# design.net
KiCad netlist of a schematic drawn in Altium Designer
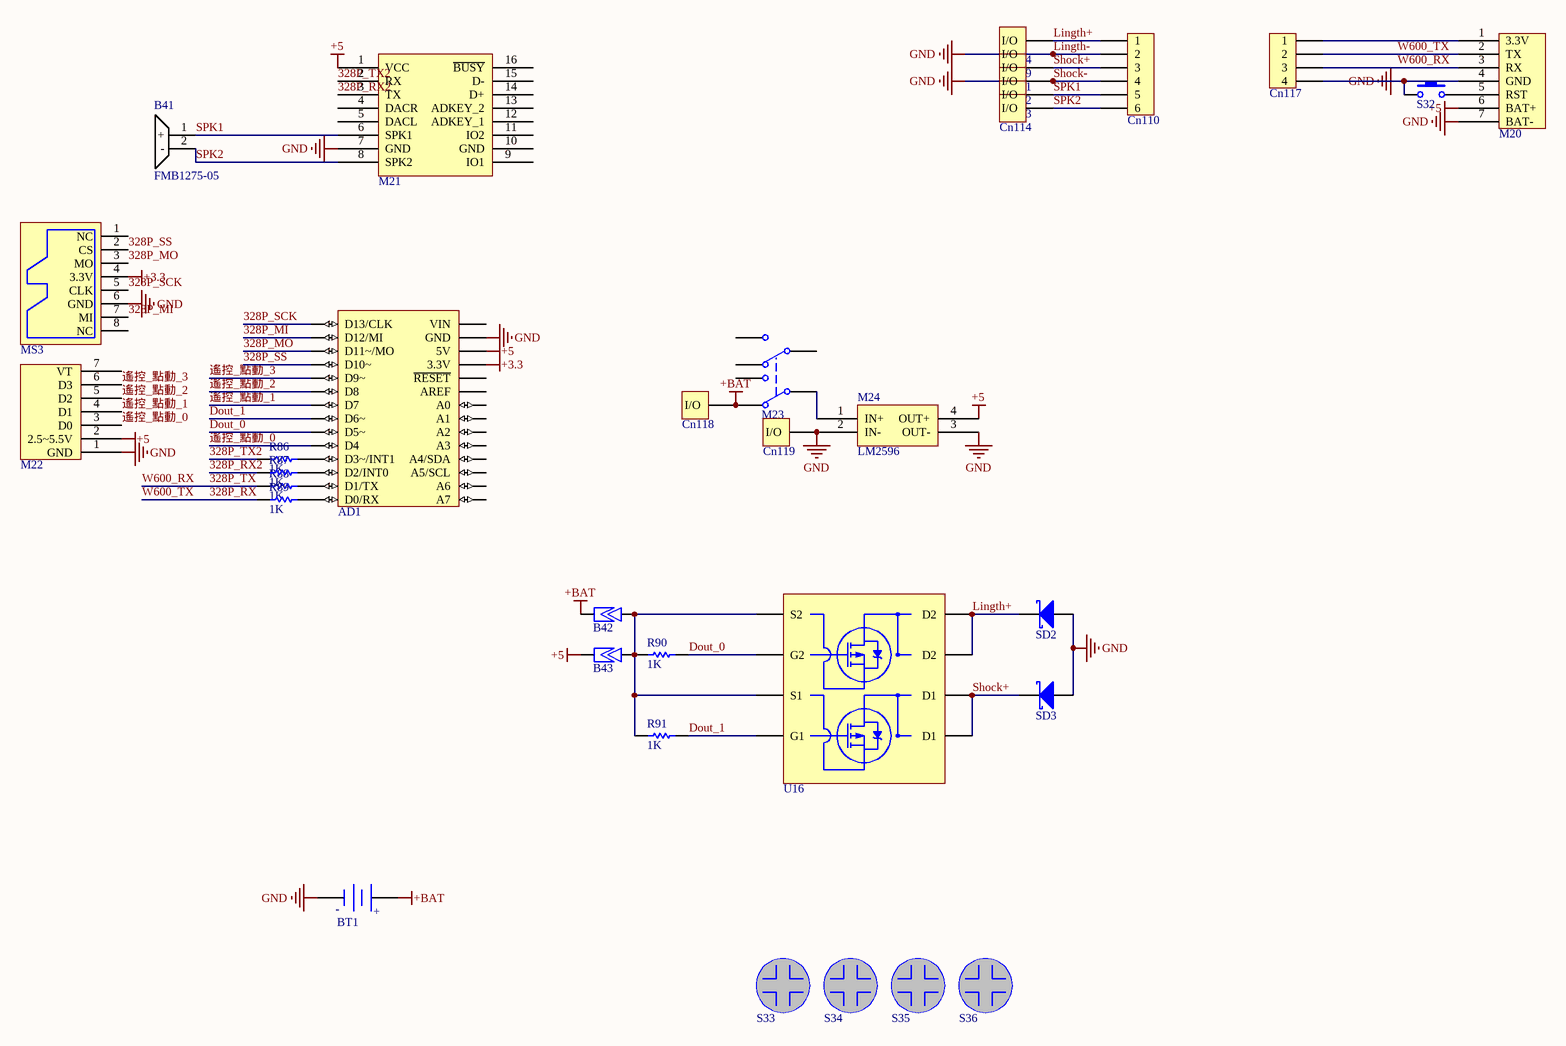
[diagram p0: 松菸_幻影光靈_屍禁_提燈.SchDoc]

(export (version "E")
  (design (tool "Eeschema 10.0.6"))
  (components
    (comp (ref "AD1")
      (value "Arduino NANO")
      (footprint "Arduino NANO")
      (description "單晶片")
      (libsource (lib "MyLibray") (part "Arduino NANO"))
    )
    (comp (ref "B41")
      (value "FMB1275-05")
      (footprint "Buzzer_12085")
      (description "無源蜂鳴器")
      (libsource (lib "MyLibray") (part "Buzzer"))
    )
    (comp (ref "B42")
      (value "短路")
      (footprint "BYPASS-0805")
      (description "短路焊點(如標註短路則需額外補錫使其短路)")
      (libsource (lib "MyLibray") (part "Bypass"))
    )
    (comp (ref "B43")
      (value "短路")
      (footprint "BYPASS-0805")
      (description "短路焊點(如標註短路則需額外補錫使其短路)")
      (libsource (lib "MyLibray") (part "Bypass"))
    )
    (comp (ref "BT1")
      (value "18650")
      (footprint "Battery_18650")
      (description "電池")
      (libsource (lib "MyLibray") (part "Battery"))
    )
    (comp (ref "Cn104")
      (value "Contact")
      (footprint "Conntact_Stamp hole_0.6\"")
      (description "接線端子、接點、郵票孔(非焊接元件)")
      (libsource (lib "MyLibray") (part "Conntact"))
    )
    (comp (ref "Cn109")
      (value "Contact")
      (footprint "Conntact_Stamp hole_0.6\"")
      (description "接線端子、接點、郵票孔(非焊接元件)")
      (libsource (lib "") (part "Conntact_1"))
    )
    (comp (ref "Cn110")
      (value "KF2510-6")
      (footprint "Connector_KF2510-6A")
      (description "連接器")
      (libsource (lib "MyLibray") (part "Conntact(6P)"))
    )
    (comp (ref "Cn111")
      (value "Contact")
      (footprint "Conntact_Stamp hole_0.6\"")
      (description "接線端子、接點、郵票孔(非焊接元件)")
      (libsource (lib "MyLibray") (part "Conntact"))
    )
    (comp (ref "Cn112")
      (value "Contact")
      (footprint "Conntact_Stamp hole_0.6\"")
      (description "接線端子、接點、郵票孔(非焊接元件)")
      (libsource (lib "MyLibray") (part "Conntact"))
    )
    (comp (ref "Cn113")
      (value "Contact")
      (footprint "Conntact_Stamp hole_0.6\"")
      (description "接線端子、接點、郵票孔(非焊接元件)")
      (libsource (lib "MyLibray") (part "Conntact"))
    )
    (comp (ref "Cn114")
      (value "Contact")
      (footprint "Conntact_Stamp hole_0.6\"")
      (description "接線端子、接點、郵票孔(非焊接元件)")
      (libsource (lib "MyLibray") (part "Conntact"))
    )
    (comp (ref "Cn117")
      (value "KF2510-4")
      (footprint "Connector_KF2510-4A")
      (description "連接器")
      (libsource (lib "MyLibray") (part "Conntact(4P)"))
    )
    (comp (ref "Cn118")
      (value "Contact")
      (footprint "Conntact_Stamp hole_0.6\"")
      (description "接線端子、接點、郵票孔(非焊接元件)")
      (libsource (lib "MyLibray") (part "Conntact"))
    )
    (comp (ref "Cn119")
      (value "Contact")
      (footprint "Conntact_Stamp hole_0.6\"")
      (description "接線端子、接點、郵票孔(非焊接元件)")
      (libsource (lib "MyLibray") (part "Conntact"))
    )
    (comp (ref "M20")
      (value "HH_W600_V2.0")
      (footprint "HH_W600_V2.0")
      (libsource (lib "MyLibray") (part "HH_W600_V2.0"))
    )
    (comp (ref "M21")
      (value "mp3-tf-16p")
      (footprint "BY8001-16P")
      (description "TTL通訊SD卡撥放mp3模組")
      (libsource (lib "MyLibray") (part "Mini MP3 Player"))
    )
    (comp (ref "M22")
      (value "XR390")
      (footprint "XR390 Module")
      (description "遙控器模組")
      (libsource (lib "MyLibray") (part "XR390"))
    )
    (comp (ref "M23")
      (value "MST22D18G2")
      (footprint "Switch_MST22D18G2")
      (description "開關_滑動_2通道")
      (libsource (lib "MyLibray") (part "Switch_Slide_2"))
    )
    (comp (ref "M24")
      (value "LM2596")
      (footprint "LM2596 Module")
      (description "DC to DC 降壓模組")
      (libsource (lib "MyLibray") (part "LM2596_Moduld"))
    )
    (comp (ref "MS3")
      (value "Interface_MicroSD card slot")
      (footprint "Interface_MicroSD card slot")
      (description "Micro SD 卡座")
      (libsource (lib "MyLibray") (part "Interface_MicroSD card slot"))
    )
    (comp (ref "R86")
      (value "1K")
      (footprint "Res-1206")
      (description "電阻")
      (libsource (lib "MyLibray") (part "Res"))
    )
    (comp (ref "R87")
      (value "1K")
      (footprint "Res-1206")
      (description "電阻")
      (libsource (lib "MyLibray") (part "Res"))
    )
    (comp (ref "R88")
      (value "1K")
      (footprint "Res-1206")
      (description "電阻")
      (libsource (lib "MyLibray") (part "Res"))
    )
    (comp (ref "R89")
      (value "1K")
      (footprint "Res-1206")
      (description "電阻")
      (libsource (lib "MyLibray") (part "Res"))
    )
    (comp (ref "R90")
      (value "1K")
      (footprint "Res-1206")
      (description "電阻")
      (libsource (lib "MyLibray") (part "Res"))
    )
    (comp (ref "R91")
      (value "1K")
      (footprint "Res-1206")
      (description "電阻")
      (libsource (lib "MyLibray") (part "Res"))
    )
    (comp (ref "S32")
      (value "Switch")
      (footprint "Switch SMD-3.6*6*2.5")
      (description "開關_按鍵")
      (libsource (lib "MyLibray") (part "Switch"))
    )
    (comp (ref "S33")
      (value "M3")
      (footprint "Screw M3")
      (description "螺絲(非焊接元件)")
      (libsource (lib "MyLibray") (part "Screw"))
    )
    (comp (ref "S34")
      (value "M3")
      (footprint "Screw M3")
      (description "螺絲(非焊接元件)")
      (libsource (lib "MyLibray") (part "Screw"))
    )
    (comp (ref "S35")
      (value "M3")
      (footprint "Screw M3")
      (description "螺絲(非焊接元件)")
      (libsource (lib "MyLibray") (part "Screw"))
    )
    (comp (ref "S36")
      (value "M3")
      (footprint "Screw M3")
      (description "螺絲(非焊接元件)")
      (libsource (lib "MyLibray") (part "Screw"))
    )
    (comp (ref "SD2")
      (value "SS56")
      (footprint "Diode_SMA")
      (description "二極體_蕭特基")
      (libsource (lib "MyLibray") (part "Diode_Schottky"))
    )
    (comp (ref "SD3")
      (value "SS56")
      (footprint "Diode_SMA")
      (description "二極體_蕭特基")
      (libsource (lib "MyLibray") (part "Diode_Schottky"))
    )
    (comp (ref "U16")
      (value "AO4801")
      (footprint "SOP-8")
      (description "MOS,雙PMOS")
      (libsource (lib "MyLibray") (part "MOS_Dual P_AO4801"))
    )
  )
  (nets
    (net (code "1") (name "+3.3") (class "Default")
      (node (ref "AD1") (pin "5") (pinfunction "3.3V_5") (pintype "passive"))
      (node (ref "MS3") (pin "4") (pinfunction "3.3V_4") (pintype "power_in"))
    )
    (net (code "2") (name "+5") (class "Default")
      (node (ref "AD1") (pin "3") (pinfunction "5V_3") (pintype "passive"))
      (node (ref "B43") (pin "1") (pinfunction "1_1") (pintype "passive"))
      (node (ref "M20") (pin "6") (pinfunction "BAT+_6") (pintype "passive"))
      (node (ref "M21") (pin "1") (pinfunction "VCC_1") (pintype "passive"))
      (node (ref "M22") (pin "2") (pinfunction "2.5~5.5V_2") (pintype "passive"))
      (node (ref "M24") (pin "4") (pinfunction "OUT+_4") (pintype "passive"))
    )
    (net (code "3") (name "+BAT") (class "Default")
      (node (ref "B42") (pin "1") (pinfunction "1_1") (pintype "passive"))
      (node (ref "BT1") (pin "1") (pinfunction "+_1") (pintype "power_in"))
      (node (ref "Cn118") (pin "1") (pinfunction "I/O_1") (pintype "passive"))
      (node (ref "M23") (pin "2") (pinfunction "2_2") (pintype "passive"))
    )
    (net (code "4") (name "/328P_MI") (class "Default")
      (node (ref "AD1") (pin "19") (pinfunction "D12/MI_19") (pintype "bidirectional"))
      (node (ref "MS3") (pin "7") (pinfunction "MI_7") (pintype "passive"))
    )
    (net (code "5") (name "/328P_MO") (class "Default")
      (node (ref "AD1") (pin "18") (pinfunction "D11~/MO_18") (pintype "bidirectional"))
      (node (ref "MS3") (pin "3") (pinfunction "MO_3") (pintype "passive"))
    )
    (net (code "6") (name "/328P_RX") (class "Default")
      (node (ref "Cn117") (pin "2") (pinfunction "2_2") (pintype "passive"))
      (node (ref "M20") (pin "2") (pinfunction "TX_2") (pintype "passive"))
      (node (ref "R89") (pin "1") (pinfunction "1_1") (pintype "passive"))
    )
    (net (code "7") (name "/328P_RX2") (class "Default")
      (node (ref "M21") (pin "3") (pinfunction "TX_3") (pintype "passive"))
      (node (ref "R87") (pin "1") (pinfunction "1_1") (pintype "passive"))
    )
    (net (code "8") (name "/328P_SCK") (class "Default")
      (node (ref "AD1") (pin "20") (pinfunction "D13/CLK_20") (pintype "bidirectional"))
      (node (ref "MS3") (pin "5") (pinfunction "CLK_5") (pintype "passive"))
    )
    (net (code "9") (name "/328P_SS") (class "Default")
      (node (ref "AD1") (pin "17") (pinfunction "D10~_17") (pintype "bidirectional"))
      (node (ref "MS3") (pin "2") (pinfunction "CS_2") (pintype "passive"))
    )
    (net (code "10") (name "/328P_TX") (class "Default")
      (node (ref "Cn117") (pin "3") (pinfunction "3_3") (pintype "passive"))
      (node (ref "M20") (pin "3") (pinfunction "RX_3") (pintype "passive"))
      (node (ref "R88") (pin "1") (pinfunction "1_1") (pintype "passive"))
    )
    (net (code "11") (name "/328P_TX2") (class "Default")
      (node (ref "M21") (pin "2") (pinfunction "RX_2") (pintype "passive"))
      (node (ref "R86") (pin "1") (pinfunction "1_1") (pintype "passive"))
    )
    (net (code "12") (name "/Dout_0") (class "Default")
      (node (ref "AD1") (pin "12") (pinfunction "D5~_12") (pintype "bidirectional"))
      (node (ref "R90") (pin "2") (pinfunction "2_2") (pintype "passive"))
      (node (ref "U16") (pin "2") (pinfunction "G2_2") (pintype "passive"))
    )
    (net (code "13") (name "/Dout_1") (class "Default")
      (node (ref "AD1") (pin "13") (pinfunction "D6~_13") (pintype "bidirectional"))
      (node (ref "R91") (pin "2") (pinfunction "2_2") (pintype "passive"))
      (node (ref "U16") (pin "4") (pinfunction "G1_4") (pintype "passive"))
    )
    (net (code "14") (name "/Lingth+") (class "Default")
      (node (ref "Cn104") (pin "1") (pinfunction "I/O_1") (pintype "passive"))
      (node (ref "Cn110") (pin "1") (pinfunction "1_1") (pintype "passive"))
      (node (ref "SD2") (pin "1") (pinfunction "K_1") (pintype "passive"))
      (node (ref "U16") (pin "7") (pinfunction "D2_7") (pintype "passive"))
      (node (ref "U16") (pin "8") (pinfunction "D2_8") (pintype "passive"))
    )
    (net (code "15") (name "/SPK1") (class "Default")
      (node (ref "B41") (pin "1") (pinfunction "+_1") (pintype "passive"))
      (node (ref "Cn110") (pin "5") (pinfunction "5_5") (pintype "passive"))
      (node (ref "Cn113") (pin "1") (pinfunction "I/O_1") (pintype "passive"))
      (node (ref "M21") (pin "6") (pinfunction "SPK1_6") (pintype "passive"))
    )
    (net (code "16") (name "/SPK2") (class "Default")
      (node (ref "B41") (pin "2") (pinfunction "-_2") (pintype "passive"))
      (node (ref "Cn110") (pin "6") (pinfunction "6_6") (pintype "passive"))
      (node (ref "Cn114") (pin "1") (pinfunction "I/O_1") (pintype "passive"))
      (node (ref "M21") (pin "8") (pinfunction "SPK2_8") (pintype "passive"))
    )
    (net (code "17") (name "/Shock+") (class "Default")
      (node (ref "Cn110") (pin "3") (pinfunction "3_3") (pintype "passive"))
      (node (ref "Cn111") (pin "1") (pinfunction "I/O_1") (pintype "passive"))
      (node (ref "SD3") (pin "1") (pinfunction "K_1") (pintype "passive"))
      (node (ref "U16") (pin "5") (pinfunction "D1_5") (pintype "passive"))
      (node (ref "U16") (pin "6") (pinfunction "D1_6") (pintype "passive"))
    )
    (net (code "18") (name "/遙控_點動_0") (class "Default")
      (node (ref "AD1") (pin "11") (pinfunction "D4_11") (pintype "bidirectional"))
      (node (ref "M22") (pin "3") (pinfunction "D0_3") (pintype "passive"))
    )
    (net (code "19") (name "/遙控_點動_1") (class "Default")
      (node (ref "AD1") (pin "14") (pinfunction "D7_14") (pintype "bidirectional"))
      (node (ref "M22") (pin "4") (pinfunction "D1_4") (pintype "passive"))
    )
    (net (code "20") (name "/遙控_點動_2") (class "Default")
      (node (ref "AD1") (pin "15") (pinfunction "D8_15") (pintype "bidirectional"))
      (node (ref "M22") (pin "5") (pinfunction "D2_5") (pintype "passive"))
    )
    (net (code "21") (name "/遙控_點動_3") (class "Default")
      (node (ref "AD1") (pin "16") (pinfunction "D9~_16") (pintype "bidirectional"))
      (node (ref "M22") (pin "6") (pinfunction "D3_6") (pintype "passive"))
    )
    (net (code "22") (name "GND") (class "Default")
      (node (ref "AD1") (pin "2") (pinfunction "GND_2") (pintype "passive"))
      (node (ref "BT1") (pin "2") (pinfunction "-_2") (pintype "power_in"))
      (node (ref "Cn109") (pin "1") (pinfunction "I/O_1") (pintype "passive"))
      (node (ref "Cn110") (pin "2") (pinfunction "2_2") (pintype "passive"))
      (node (ref "Cn110") (pin "4") (pinfunction "4_4") (pintype "passive"))
      (node (ref "Cn112") (pin "1") (pinfunction "I/O_1") (pintype "passive"))
      (node (ref "Cn117") (pin "4") (pinfunction "4_4") (pintype "passive"))
      (node (ref "Cn119") (pin "1") (pinfunction "I/O_1") (pintype "passive"))
      (node (ref "M20") (pin "4") (pinfunction "GND_4") (pintype "passive"))
      (node (ref "M20") (pin "7") (pinfunction "BAT-_7") (pintype "passive"))
      (node (ref "M21") (pin "7") (pinfunction "GND_7") (pintype "passive"))
      (node (ref "M22") (pin "1") (pinfunction "GND_1") (pintype "passive"))
      (node (ref "M24") (pin "2") (pinfunction "IN-_2") (pintype "passive"))
      (node (ref "M24") (pin "3") (pinfunction "OUT-_3") (pintype "passive"))
      (node (ref "MS3") (pin "6") (pinfunction "GND_6") (pintype "power_in"))
      (node (ref "S32") (pin "1") (pinfunction "1_1") (pintype "passive"))
      (node (ref "SD2") (pin "2") (pinfunction "A_2") (pintype "passive"))
      (node (ref "SD3") (pin "2") (pinfunction "A_2") (pintype "passive"))
    )
    (net (code "23") (name "Net-(AD1-D0{slash}RX)") (class "Default")
      (node (ref "AD1") (pin "7") (pinfunction "D0/RX_7") (pintype "bidirectional"))
      (node (ref "R89") (pin "2") (pinfunction "2_2") (pintype "passive"))
    )
    (net (code "24") (name "Net-(AD1-D1{slash}TX)") (class "Default")
      (node (ref "AD1") (pin "8") (pinfunction "D1/TX_8") (pintype "bidirectional"))
      (node (ref "R88") (pin "2") (pinfunction "2_2") (pintype "passive"))
    )
    (net (code "25") (name "Net-(AD1-D2{slash}INT0)") (class "Default")
      (node (ref "AD1") (pin "9") (pinfunction "D2/INT0_9") (pintype "bidirectional"))
      (node (ref "R87") (pin "2") (pinfunction "2_2") (pintype "passive"))
    )
    (net (code "26") (name "Net-(AD1-D3~{slash}INT1)") (class "Default")
      (node (ref "AD1") (pin "10") (pinfunction "D3~/INT1_10") (pintype "bidirectional"))
      (node (ref "R86") (pin "2") (pinfunction "2_2") (pintype "passive"))
    )
    (net (code "27") (name "Net-(M20-3.3V)") (class "Default")
      (node (ref "Cn117") (pin "1") (pinfunction "1_1") (pintype "passive"))
      (node (ref "M20") (pin "1") (pinfunction "3.3V_1") (pintype "passive"))
    )
    (net (code "28") (name "Net-(M20-RST)") (class "Default")
      (node (ref "M20") (pin "5") (pinfunction "RST_5") (pintype "passive"))
      (node (ref "S32") (pin "2") (pinfunction "2_2") (pintype "passive"))
    )
    (net (code "29") (name "Net-(M24-IN+)") (class "Default")
      (node (ref "M23") (pin "1") (pinfunction "1_1") (pintype "passive"))
      (node (ref "M24") (pin "1") (pinfunction "IN+_1") (pintype "passive"))
    )
    (net (code "30") (name "Net-(U16-S1)") (class "Default")
      (node (ref "B42") (pin "2") (pinfunction "2_2") (pintype "passive"))
      (node (ref "B43") (pin "2") (pinfunction "2_2") (pintype "passive"))
      (node (ref "R90") (pin "1") (pinfunction "1_1") (pintype "passive"))
      (node (ref "R91") (pin "1") (pinfunction "1_1") (pintype "passive"))
      (node (ref "U16") (pin "1") (pinfunction "S2_1") (pintype "passive"))
      (node (ref "U16") (pin "3") (pinfunction "S1_3") (pintype "passive"))
    )
    (net (code "31") (name "unconnected-(AD1-A0-Pad21)") (class "Default")
      (node (ref "AD1") (pin "21") (pinfunction "A0_21") (pintype "bidirectional"))
    )
    (net (code "32") (name "unconnected-(AD1-A1-Pad22)") (class "Default")
      (node (ref "AD1") (pin "22") (pinfunction "A1_22") (pintype "bidirectional"))
    )
    (net (code "33") (name "unconnected-(AD1-A2-Pad23)") (class "Default")
      (node (ref "AD1") (pin "23") (pinfunction "A2_23") (pintype "bidirectional"))
    )
    (net (code "34") (name "unconnected-(AD1-A3-Pad24)") (class "Default")
      (node (ref "AD1") (pin "24") (pinfunction "A3_24") (pintype "bidirectional"))
    )
    (net (code "35") (name "unconnected-(AD1-A4{slash}SDA-Pad25)") (class "Default")
      (node (ref "AD1") (pin "25") (pinfunction "A4/SDA_25") (pintype "bidirectional"))
    )
    (net (code "36") (name "unconnected-(AD1-A5{slash}SCL-Pad26)") (class "Default")
      (node (ref "AD1") (pin "26") (pinfunction "A5/SCL_26") (pintype "bidirectional"))
    )
    (net (code "37") (name "unconnected-(AD1-A6-Pad27)") (class "Default")
      (node (ref "AD1") (pin "27") (pinfunction "A6_27") (pintype "bidirectional"))
    )
    (net (code "38") (name "unconnected-(AD1-A7-Pad28)") (class "Default")
      (node (ref "AD1") (pin "28") (pinfunction "A7_28") (pintype "bidirectional"))
    )
    (net (code "39") (name "unconnected-(AD1-AREF-Pad6)") (class "Default")
      (node (ref "AD1") (pin "6") (pinfunction "AREF_6") (pintype "passive"))
    )
    (net (code "40") (name "unconnected-(AD1-VIN-Pad1)") (class "Default")
      (node (ref "AD1") (pin "1") (pinfunction "VIN_1") (pintype "passive"))
    )
    (net (code "41") (name "unconnected-(AD1-~{RESET}-Pad4)") (class "Default")
      (node (ref "AD1") (pin "4") (pinfunction "~{RESET}_4") (pintype "passive"))
    )
    (net (code "42") (name "unconnected-(M21-ADKEY_1-Pad12)") (class "Default")
      (node (ref "M21") (pin "12") (pinfunction "ADKEY_1_12") (pintype "passive"))
    )
    (net (code "43") (name "unconnected-(M21-ADKEY_2-Pad13)") (class "Default")
      (node (ref "M21") (pin "13") (pinfunction "ADKEY_2_13") (pintype "passive"))
    )
    (net (code "44") (name "unconnected-(M21-D+-Pad14)") (class "Default")
      (node (ref "M21") (pin "14") (pinfunction "D+_14") (pintype "passive"))
    )
    (net (code "45") (name "unconnected-(M21-D--Pad15)") (class "Default")
      (node (ref "M21") (pin "15") (pinfunction "D-_15") (pintype "passive"))
    )
    (net (code "46") (name "unconnected-(M21-DACL-Pad5)") (class "Default")
      (node (ref "M21") (pin "5") (pinfunction "DACL_5") (pintype "passive"))
    )
    (net (code "47") (name "unconnected-(M21-DACR-Pad4)") (class "Default")
      (node (ref "M21") (pin "4") (pinfunction "DACR_4") (pintype "passive"))
    )
    (net (code "48") (name "unconnected-(M21-GND-Pad10)") (class "Default")
      (node (ref "M21") (pin "10") (pinfunction "GND_10") (pintype "passive"))
    )
    (net (code "49") (name "unconnected-(M21-IO1-Pad9)") (class "Default")
      (node (ref "M21") (pin "9") (pinfunction "IO1_9") (pintype "passive"))
    )
    (net (code "50") (name "unconnected-(M21-IO2-Pad11)") (class "Default")
      (node (ref "M21") (pin "11") (pinfunction "IO2_11") (pintype "passive"))
    )
    (net (code "51") (name "unconnected-(M21-~{BUSY}-Pad16)") (class "Default")
      (node (ref "M21") (pin "16") (pinfunction "~{BUSY}_16") (pintype "passive"))
    )
    (net (code "52") (name "unconnected-(M22-VT-Pad7)") (class "Default")
      (node (ref "M22") (pin "7") (pinfunction "VT_7") (pintype "passive"))
    )
    (net (code "53") (name "unconnected-(M23-Pad3)") (class "Default")
      (node (ref "M23") (pin "3") (pinfunction "3_3") (pintype "passive"))
    )
    (net (code "54") (name "unconnected-(M23-Pad4)") (class "Default")
      (node (ref "M23") (pin "4") (pinfunction "4_4") (pintype "passive"))
    )
    (net (code "55") (name "unconnected-(M23-Pad5)") (class "Default")
      (node (ref "M23") (pin "5") (pinfunction "5_5") (pintype "passive"))
    )
    (net (code "56") (name "unconnected-(M23-Pad6)") (class "Default")
      (node (ref "M23") (pin "6") (pinfunction "6_6") (pintype "passive"))
    )
    (net (code "57") (name "unconnected-(MS3-NC-Pad1)") (class "Default")
      (node (ref "MS3") (pin "1") (pinfunction "NC_1") (pintype "passive"))
    )
    (net (code "58") (name "unconnected-(MS3-NC-Pad8)") (class "Default")
      (node (ref "MS3") (pin "8") (pinfunction "NC_8") (pintype "passive"))
    )
  )
)
